# VSAB_N64ADV.net
KiCad netlist of a schematic drawn in EAGLE
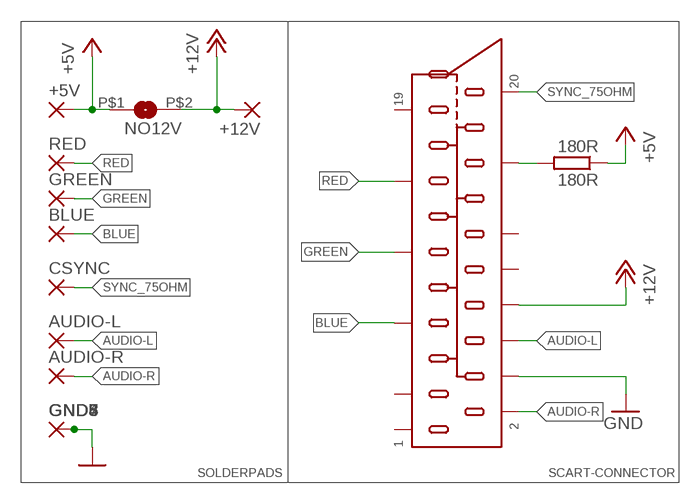
[diagram p0: schematic, sheet 1]

(export (version "E")
  (design (tool "Eeschema 10.0.6"))
  (components
    (comp (ref "+5V")
      (value "WIREPADSMD5-1,8")
      (footprint "eagle-import:5-1,8")
      (libsource (lib "eagle-import") (part "WIREPADSMD5-1,8"))
    )
    (comp (ref "+12V")
      (value "WIREPADSMD5-1,8")
      (footprint "eagle-import:5-1,8")
      (libsource (lib "eagle-import") (part "WIREPADSMD5-1,8"))
    )
    (comp (ref "180R")
      (value "180R")
      (footprint "eagle-import:R0805")
      (libsource (lib "eagle-import") (part "R-EU_R0805"))
    )
    (comp (ref "AUDIO-L")
      (value "WIREPADSMD5-1,8")
      (footprint "eagle-import:5-1,8")
      (libsource (lib "eagle-import") (part "WIREPADSMD5-1,8"))
    )
    (comp (ref "AUDIO-R")
      (value "WIREPADSMD5-1,8")
      (footprint "eagle-import:5-1,8")
      (libsource (lib "eagle-import") (part "WIREPADSMD5-1,8"))
    )
    (comp (ref "BLUE")
      (value "WIREPADSMD5-1,8")
      (footprint "eagle-import:5-1,8")
      (libsource (lib "eagle-import") (part "WIREPADSMD5-1,8"))
    )
    (comp (ref "CSYNC")
      (value "WIREPADSMD5-1,8")
      (footprint "eagle-import:5-1,8")
      (libsource (lib "eagle-import") (part "WIREPADSMD5-1,8"))
    )
    (comp (ref "GND")
      (value "WIREPADSMD5-1,8")
      (footprint "eagle-import:5-1,8")
      (libsource (lib "eagle-import") (part "WIREPADSMD5-1,8"))
    )
    (comp (ref "GND3")
      (value "WIREPADSMD5-1,8")
      (footprint "eagle-import:5-1,8")
      (libsource (lib "eagle-import") (part "WIREPADSMD5-1,8"))
    )
    (comp (ref "GND4")
      (value "WIREPADSMD5-1,8")
      (footprint "eagle-import:5-1,8")
      (libsource (lib "eagle-import") (part "WIREPADSMD5-1,8"))
    )
    (comp (ref "GND5")
      (value "WIREPADSMD5-1,8")
      (footprint "eagle-import:5-1,8")
      (libsource (lib "eagle-import") (part "WIREPADSMD5-1,8"))
    )
    (comp (ref "GND6")
      (value "WIREPADSMD5-1,8")
      (footprint "eagle-import:5-1,8")
      (libsource (lib "eagle-import") (part "WIREPADSMD5-1,8"))
    )
    (comp (ref "GND7")
      (value "WIREPADSMD5-1,8")
      (footprint "eagle-import:5-1,8")
      (libsource (lib "eagle-import") (part "WIREPADSMD5-1,8"))
    )
    (comp (ref "GND8")
      (value "WIREPADSMD5-1,8")
      (footprint "eagle-import:5-1,8")
      (libsource (lib "eagle-import") (part "WIREPADSMD5-1,8"))
    )
    (comp (ref "GREEN")
      (value "WIREPADSMD5-1,8")
      (footprint "eagle-import:5-1,8")
      (libsource (lib "eagle-import") (part "WIREPADSMD5-1,8"))
    )
    (comp (ref "NO12V")
      (value "MY_JUMPER")
      (footprint "eagle-import:MYJUMP")
      (libsource (lib "eagle-import") (part "MY_JUMPER"))
    )
    (comp (ref "RED")
      (value "WIREPADSMD5-1,8")
      (footprint "eagle-import:5-1,8")
      (libsource (lib "eagle-import") (part "WIREPADSMD5-1,8"))
    )
    (comp (ref "U$2")
      (value "SCART_PLUG")
      (footprint "eagle-import:SCART")
      (libsource (lib "eagle-import") (part "SCART_PLUG"))
    )
  )
  (nets
    (net (code "1") (name "+5V") (class "Default")
      (node (ref "+5V") (pin "1") (pinfunction "P_1") (pintype "passive"))
      (node (ref "180R") (pin "1") (pinfunction "1_1") (pintype "passive"))
      (node (ref "NO12V") (pin "P$1") (pinfunction "1_P$1") (pintype "passive"))
    )
    (net (code "2") (name "+12V") (class "Default")
      (node (ref "+12V") (pin "1") (pinfunction "P_1") (pintype "passive"))
      (node (ref "NO12V") (pin "P$2") (pinfunction "2_P$2") (pintype "passive"))
      (node (ref "U$2") (pin "8") (pinfunction "TV/AV_SW_8") (pintype "bidirectional"))
    )
    (net (code "3") (name "AUDIO-L") (class "Default")
      (node (ref "AUDIO-L") (pin "1") (pinfunction "P_1") (pintype "passive"))
      (node (ref "U$2") (pin "6") (pinfunction "AUDIO_IN_L_6") (pintype "bidirectional"))
    )
    (net (code "4") (name "AUDIO-R") (class "Default")
      (node (ref "AUDIO-R") (pin "1") (pinfunction "P_1") (pintype "passive"))
      (node (ref "U$2") (pin "2") (pinfunction "AUDIO_IN_R_2") (pintype "bidirectional"))
    )
    (net (code "5") (name "BLUE") (class "Default")
      (node (ref "BLUE") (pin "1") (pinfunction "P_1") (pintype "passive"))
      (node (ref "U$2") (pin "7") (pinfunction "RGB_BLUE/YUV_V/PB_7") (pintype "bidirectional"))
    )
    (net (code "6") (name "GND") (class "Default")
      (node (ref "GND") (pin "1") (pinfunction "P_1") (pintype "passive"))
      (node (ref "GND3") (pin "1") (pinfunction "P_1") (pintype "passive"))
      (node (ref "GND4") (pin "1") (pinfunction "P_1") (pintype "passive"))
      (node (ref "GND5") (pin "1") (pinfunction "P_1") (pintype "passive"))
      (node (ref "GND6") (pin "1") (pinfunction "P_1") (pintype "passive"))
      (node (ref "GND7") (pin "1") (pinfunction "P_1") (pintype "passive"))
      (node (ref "GND8") (pin "1") (pinfunction "P_1") (pintype "passive"))
      (node (ref "U$2") (pin "13") (pinfunction "GND_13") (pintype "bidirectional"))
      (node (ref "U$2") (pin "14") (pinfunction "GND_14") (pintype "bidirectional"))
      (node (ref "U$2") (pin "17") (pinfunction "GND_17") (pintype "bidirectional"))
      (node (ref "U$2") (pin "18") (pinfunction "GND_18") (pintype "bidirectional"))
      (node (ref "U$2") (pin "4") (pinfunction "GND_4") (pintype "bidirectional"))
      (node (ref "U$2") (pin "5") (pinfunction "GND_5") (pintype "bidirectional"))
      (node (ref "U$2") (pin "9") (pinfunction "GND_9") (pintype "bidirectional"))
    )
    (net (code "7") (name "GREEN") (class "Default")
      (node (ref "GREEN") (pin "1") (pinfunction "P_1") (pintype "passive"))
      (node (ref "U$2") (pin "11") (pinfunction "RGB_GREEN/YUV-Y_11") (pintype "bidirectional"))
    )
    (net (code "8") (name "Net-(U$2-AV{slash}RGB_SW)") (class "Default")
      (node (ref "180R") (pin "2") (pinfunction "2_2") (pintype "passive"))
      (node (ref "U$2") (pin "16") (pinfunction "AV/RGB_SW_16") (pintype "bidirectional"))
    )
    (net (code "9") (name "RED") (class "Default")
      (node (ref "RED") (pin "1") (pinfunction "P_1") (pintype "passive"))
      (node (ref "U$2") (pin "15") (pinfunction "RGB_RED/YUV-U/PR/CHROMA_15") (pintype "bidirectional"))
    )
    (net (code "10") (name "SYNC_75OHM") (class "Default")
      (node (ref "CSYNC") (pin "1") (pinfunction "P_1") (pintype "passive"))
      (node (ref "U$2") (pin "20") (pinfunction "COMP/SYNC/LUMA_IN_20") (pintype "bidirectional"))
    )
    (net (code "11") (name "unconnected-(U$2-ADUIO_OUT_R-Pad1)") (class "Default")
      (node (ref "U$2") (pin "1") (pinfunction "ADUIO_OUT_R_1") (pintype "bidirectional"))
    )
    (net (code "12") (name "unconnected-(U$2-AUDIO_OUT_L-Pad3)") (class "Default")
      (node (ref "U$2") (pin "3") (pinfunction "AUDIO_OUT_L_3") (pintype "bidirectional"))
    )
    (net (code "13") (name "unconnected-(U$2-COMP{slash}SNYC{slash}LUMA_OUT-Pad19)") (class "Default")
      (node (ref "U$2") (pin "19") (pinfunction "COMP/SNYC/LUMA_OUT_19") (pintype "bidirectional"))
    )
    (net (code "14") (name "unconnected-(U$2-D2B_IN-Pad10)") (class "Default")
      (node (ref "U$2") (pin "10") (pinfunction "D2B_IN_10") (pintype "bidirectional"))
    )
    (net (code "15") (name "unconnected-(U$2-D2B_OUT-Pad12)") (class "Default")
      (node (ref "U$2") (pin "12") (pinfunction "D2B_OUT_12") (pintype "bidirectional"))
    )
  )
)
